# Display.net
KiCad netlist of a schematic drawn in Altium Designer
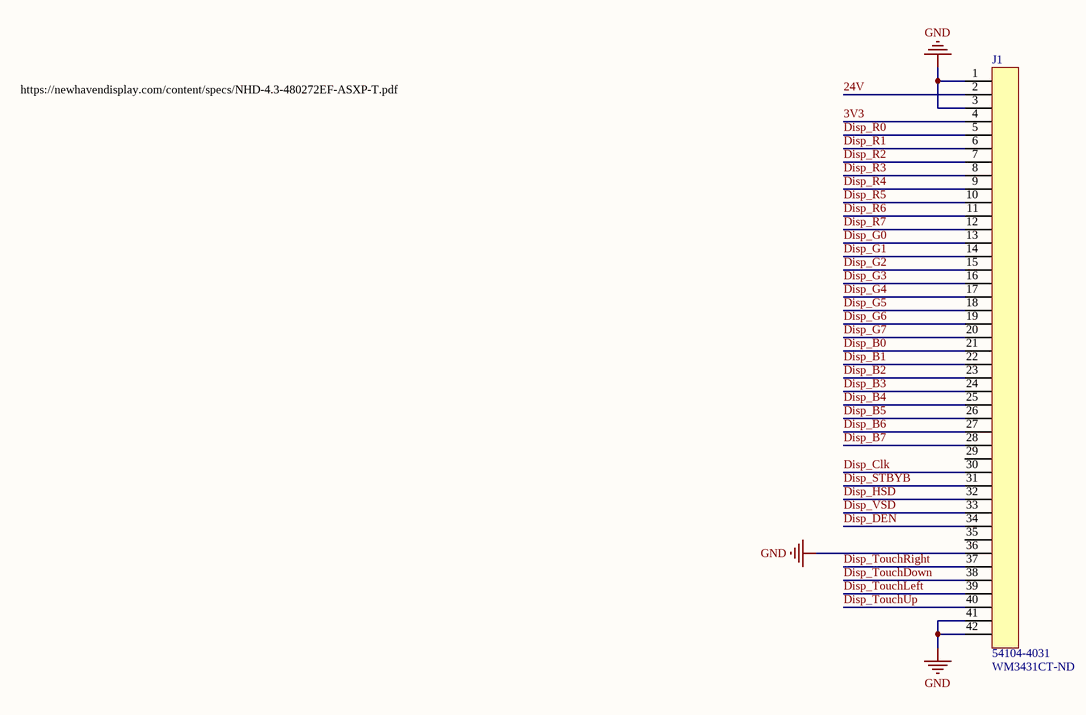
[diagram p0: Display.SchDoc]

(export (version "E")
  (design (tool "Eeschema 10.0.6"))
  (components
    (comp (ref "J1")
      (value "54104-4031")
      (description "Conn FFC/FPC Connector SKT 40 POS 0.5mm Solder RA SMD Easy-On™ T/R")
      (fields (field (name "MANUFACTURER") "Molex") (field (name "SUPPLIER PART NUMBER 1") "WM3431CT-ND"))
      (libsource (lib "Schlib1") (part "54104-4031"))
    )
  )
  (nets
    (net (code "1") (name "/3V3") (class "Default")
      (node (ref "J1") (pin "4") (pinfunction "4_4") (pintype "passive"))
    )
    (net (code "2") (name "/24V") (class "Default")
      (node (ref "J1") (pin "2") (pinfunction "2_2") (pintype "passive"))
    )
    (net (code "4") (name "/Disp_B0") (class "Default")
      (node (ref "J1") (pin "21") (pinfunction "21_21") (pintype "passive"))
    )
    (net (code "5") (name "/Disp_B1") (class "Default")
      (node (ref "J1") (pin "22") (pinfunction "22_22") (pintype "passive"))
    )
    (net (code "6") (name "/Disp_B2") (class "Default")
      (node (ref "J1") (pin "23") (pinfunction "23_23") (pintype "passive"))
    )
    (net (code "7") (name "/Disp_B3") (class "Default")
      (node (ref "J1") (pin "24") (pinfunction "24_24") (pintype "passive"))
    )
    (net (code "8") (name "/Disp_B4") (class "Default")
      (node (ref "J1") (pin "25") (pinfunction "25_25") (pintype "passive"))
    )
    (net (code "9") (name "/Disp_B5") (class "Default")
      (node (ref "J1") (pin "26") (pinfunction "26_26") (pintype "passive"))
    )
    (net (code "10") (name "/Disp_B6") (class "Default")
      (node (ref "J1") (pin "27") (pinfunction "27_27") (pintype "passive"))
    )
    (net (code "11") (name "/Disp_B7") (class "Default")
      (node (ref "J1") (pin "28") (pinfunction "28_28") (pintype "passive"))
    )
    (net (code "12") (name "/Disp_Clk") (class "Default")
      (node (ref "J1") (pin "30") (pinfunction "30_30") (pintype "passive"))
    )
    (net (code "13") (name "/Disp_DEN") (class "Default")
      (node (ref "J1") (pin "34") (pinfunction "34_34") (pintype "passive"))
    )
    (net (code "14") (name "/Disp_G0") (class "Default")
      (node (ref "J1") (pin "13") (pinfunction "13_13") (pintype "passive"))
    )
    (net (code "15") (name "/Disp_G1") (class "Default")
      (node (ref "J1") (pin "14") (pinfunction "14_14") (pintype "passive"))
    )
    (net (code "16") (name "/Disp_G2") (class "Default")
      (node (ref "J1") (pin "15") (pinfunction "15_15") (pintype "passive"))
    )
    (net (code "17") (name "/Disp_G3") (class "Default")
      (node (ref "J1") (pin "16") (pinfunction "16_16") (pintype "passive"))
    )
    (net (code "18") (name "/Disp_G4") (class "Default")
      (node (ref "J1") (pin "17") (pinfunction "17_17") (pintype "passive"))
    )
    (net (code "19") (name "/Disp_G5") (class "Default")
      (node (ref "J1") (pin "18") (pinfunction "18_18") (pintype "passive"))
    )
    (net (code "20") (name "/Disp_G6") (class "Default")
      (node (ref "J1") (pin "19") (pinfunction "19_19") (pintype "passive"))
    )
    (net (code "21") (name "/Disp_G7") (class "Default")
      (node (ref "J1") (pin "20") (pinfunction "20_20") (pintype "passive"))
    )
    (net (code "22") (name "/Disp_HSD") (class "Default")
      (node (ref "J1") (pin "32") (pinfunction "32_32") (pintype "passive"))
    )
    (net (code "23") (name "/Disp_R0") (class "Default")
      (node (ref "J1") (pin "5") (pinfunction "5_5") (pintype "passive"))
    )
    (net (code "24") (name "/Disp_R1") (class "Default")
      (node (ref "J1") (pin "6") (pinfunction "6_6") (pintype "passive"))
    )
    (net (code "25") (name "/Disp_R2") (class "Default")
      (node (ref "J1") (pin "7") (pinfunction "7_7") (pintype "passive"))
    )
    (net (code "26") (name "/Disp_R3") (class "Default")
      (node (ref "J1") (pin "8") (pinfunction "8_8") (pintype "passive"))
    )
    (net (code "27") (name "/Disp_R4") (class "Default")
      (node (ref "J1") (pin "9") (pinfunction "9_9") (pintype "passive"))
    )
    (net (code "28") (name "/Disp_R5") (class "Default")
      (node (ref "J1") (pin "10") (pinfunction "10_10") (pintype "passive"))
    )
    (net (code "29") (name "/Disp_R6") (class "Default")
      (node (ref "J1") (pin "11") (pinfunction "11_11") (pintype "passive"))
    )
    (net (code "30") (name "/Disp_R7") (class "Default")
      (node (ref "J1") (pin "12") (pinfunction "12_12") (pintype "passive"))
    )
    (net (code "31") (name "/Disp_STBYB") (class "Default")
      (node (ref "J1") (pin "31") (pinfunction "31_31") (pintype "passive"))
    )
    (net (code "32") (name "/Disp_TouchDown") (class "Default")
      (node (ref "J1") (pin "38") (pinfunction "38_38") (pintype "passive"))
    )
    (net (code "33") (name "/Disp_TouchLeft") (class "Default")
      (node (ref "J1") (pin "39") (pinfunction "39_39") (pintype "passive"))
    )
    (net (code "34") (name "/Disp_TouchRight") (class "Default")
      (node (ref "J1") (pin "37") (pinfunction "37_37") (pintype "passive"))
    )
    (net (code "35") (name "/Disp_TouchUp") (class "Default")
      (node (ref "J1") (pin "40") (pinfunction "40_40") (pintype "passive"))
    )
    (net (code "36") (name "/Disp_VSD") (class "Default")
      (node (ref "J1") (pin "33") (pinfunction "33_33") (pintype "passive"))
    )
    (net (code "37") (name "GND") (class "Default")
      (node (ref "J1") (pin "1") (pinfunction "1_1") (pintype "passive"))
      (node (ref "J1") (pin "3") (pinfunction "3_3") (pintype "passive"))
      (node (ref "J1") (pin "36") (pinfunction "36_36") (pintype "passive"))
      (node (ref "J1") (pin "41") (pinfunction "41_41") (pintype "passive"))
      (node (ref "J1") (pin "42") (pinfunction "42_42") (pintype "passive"))
    )
    (net (code "38") (name "unconnected-(J1-Pad29)") (class "Default")
      (node (ref "J1") (pin "29") (pinfunction "29_29") (pintype "passive"))
    )
    (net (code "39") (name "unconnected-(J1-Pad35)") (class "Default")
      (node (ref "J1") (pin "35") (pinfunction "35_35") (pintype "passive"))
    )
  )
)
